# v7-flex2811.net
KiCad netlist of a schematic drawn in EAGLE
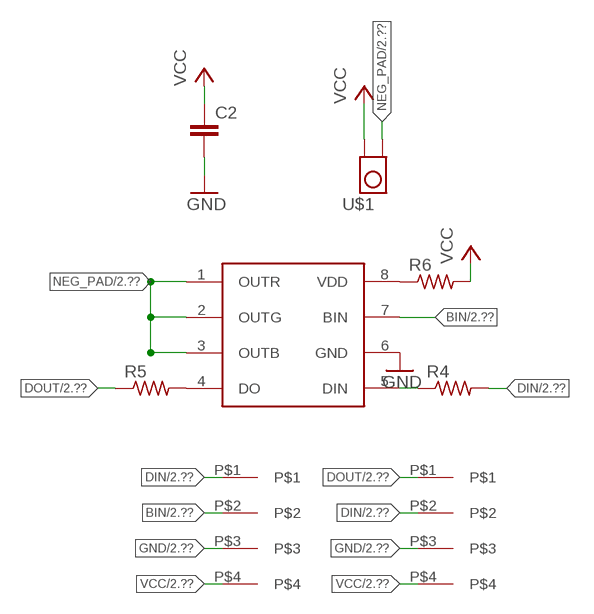
[diagram p0: schematic, sheet 1]
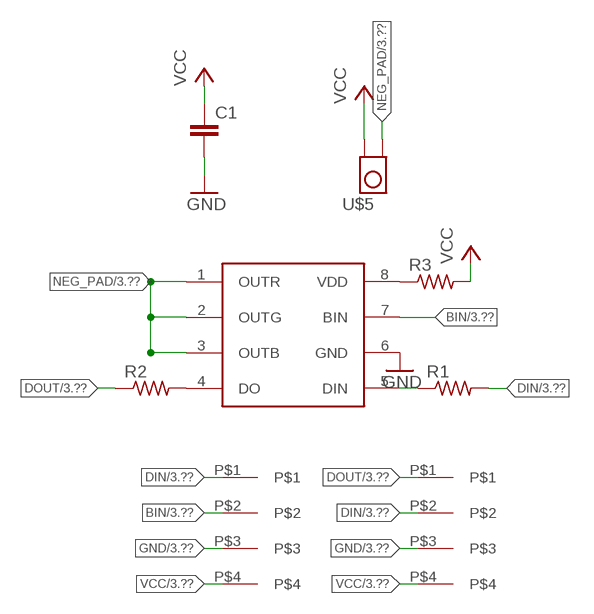
[diagram p1: schematic, sheet 2]
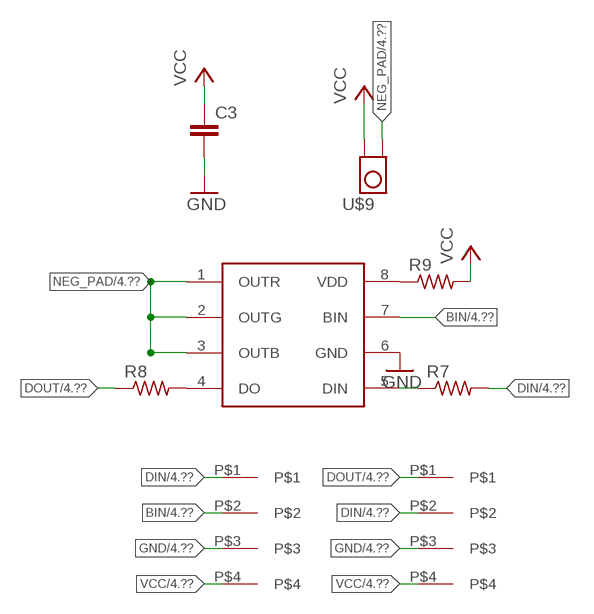
[diagram p2: schematic, sheet 3]
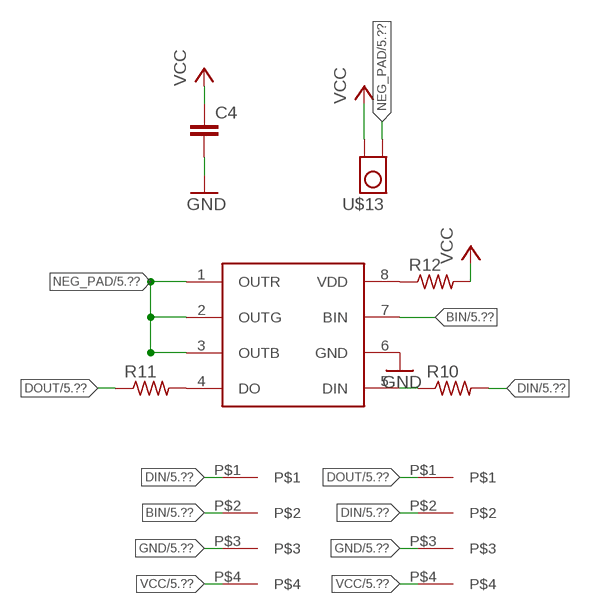
[diagram p3: schematic, sheet 4]
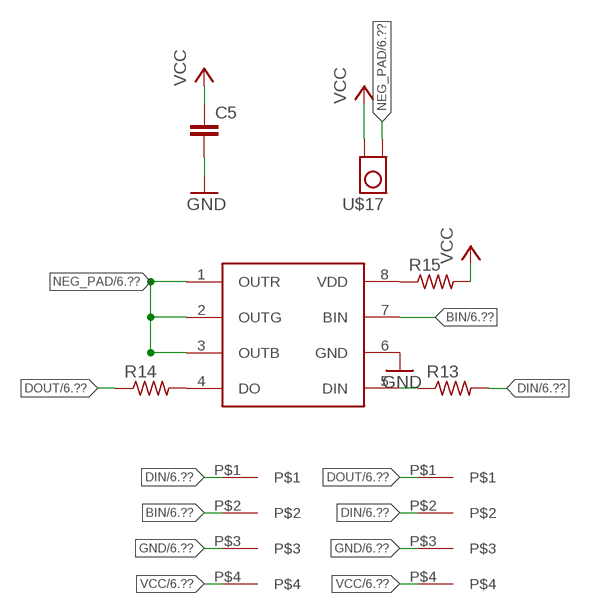
[diagram p4: schematic, sheet 5]
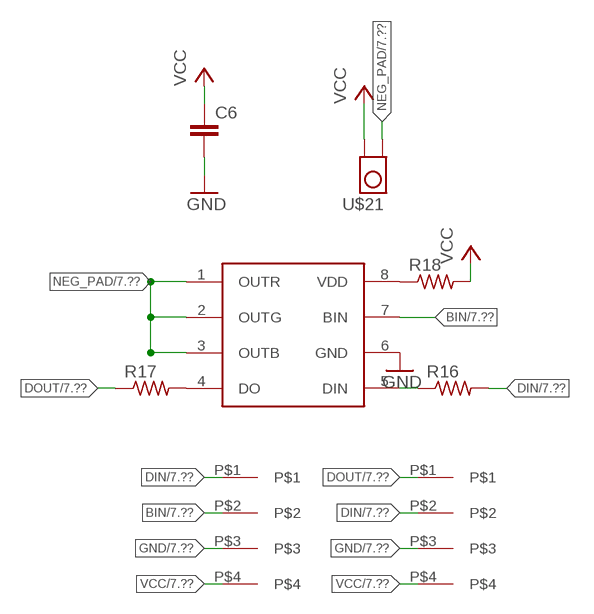
[diagram p5: schematic, sheet 6]
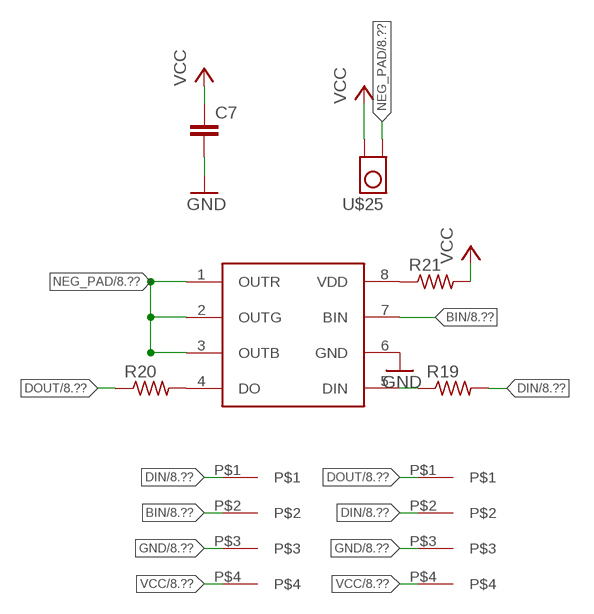
[diagram p6: schematic, sheet 7]
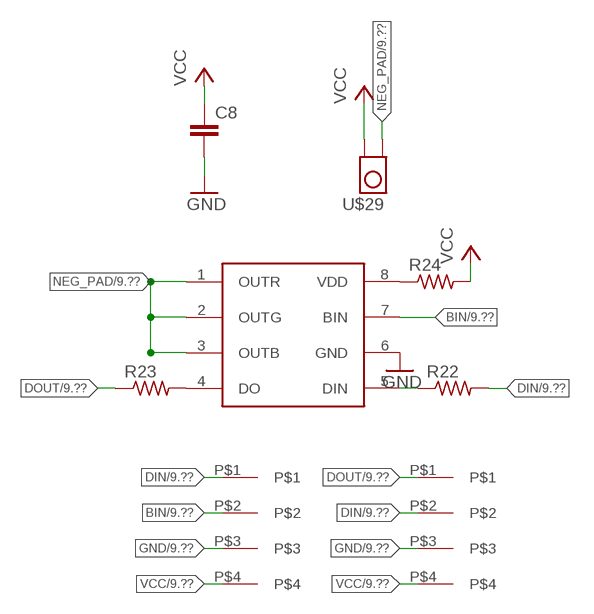
[diagram p7: schematic, sheet 8]
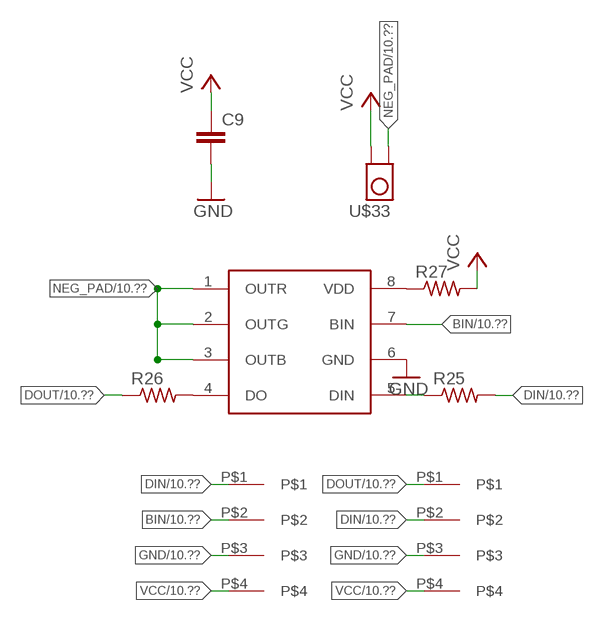
[diagram p8: schematic, sheet 9]
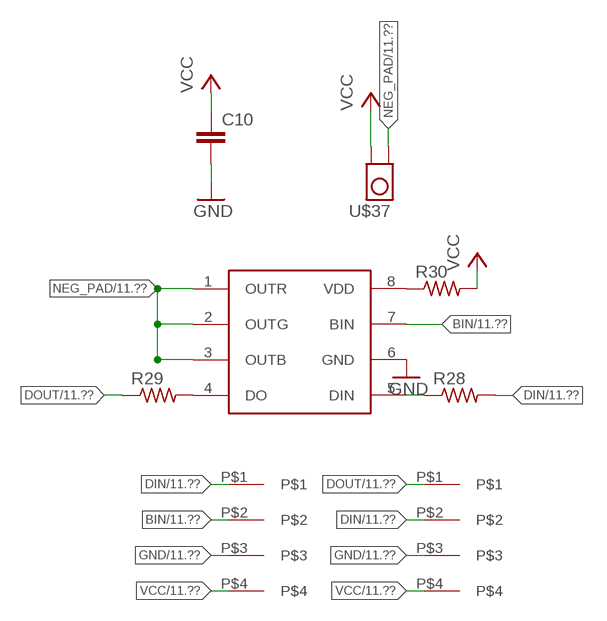
[diagram p9: schematic, sheet 10]
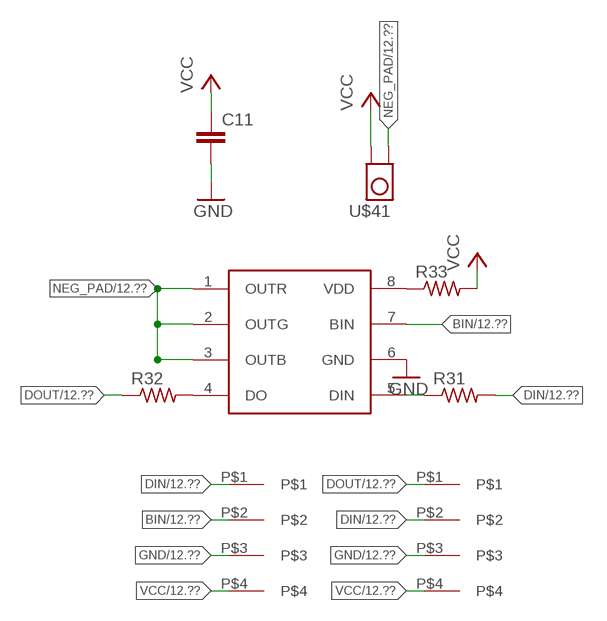
[diagram p10: schematic, sheet 11]
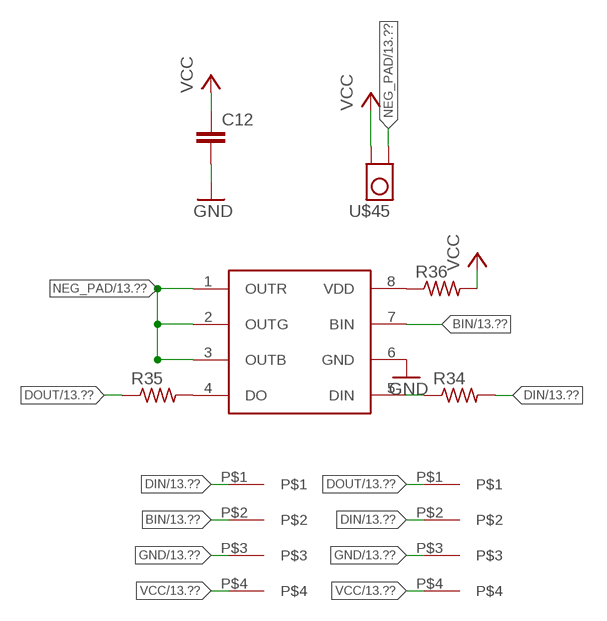
[diagram p11: schematic, sheet 12]
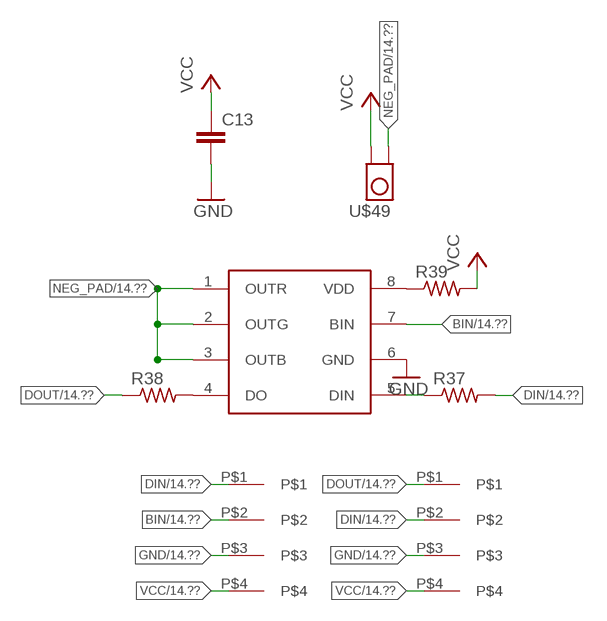
[diagram p12: schematic, sheet 13]
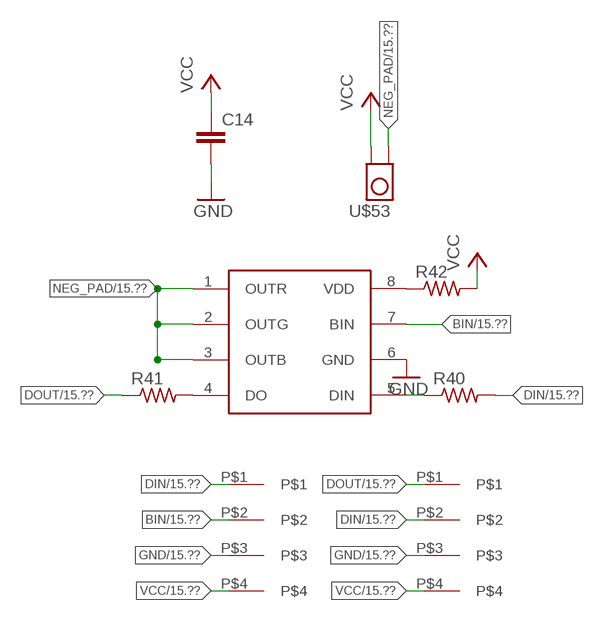
[diagram p13: schematic, sheet 14]
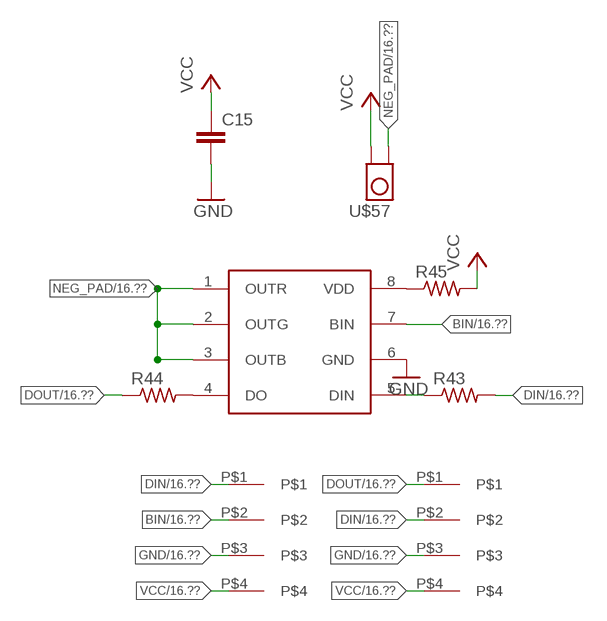
[diagram p14: schematic, sheet 15]
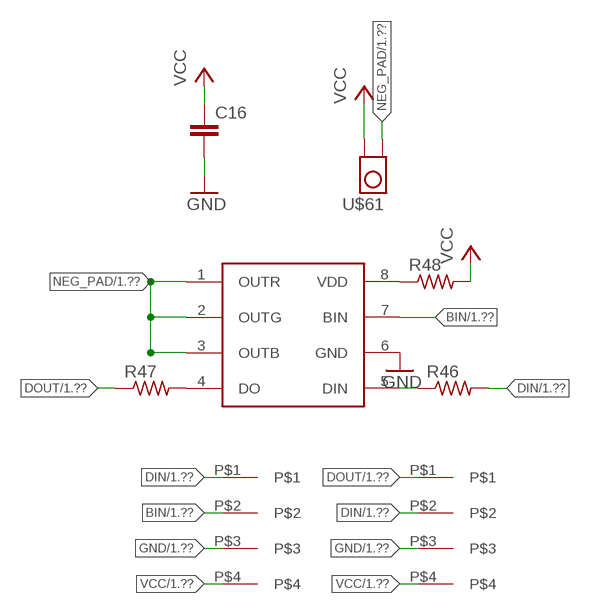
[diagram p15: schematic, sheet 16]

(export (version "E")
  (design (tool "Eeschema 10.0.6"))
  (components
    (comp (ref "C2")
      (value "C-EUC0201")
      (footprint "eagle-import:C0201")
      (libsource (lib "eagle-import") (part "C-EUC0201"))
    )
    (comp (ref "R4")
      (value "R-US_R0201")
      (footprint "eagle-import:R0201")
      (libsource (lib "eagle-import") (part "R-US_R0201"))
    )
    (comp (ref "R5")
      (value "R-US_R0201")
      (footprint "eagle-import:R0201")
      (libsource (lib "eagle-import") (part "R-US_R0201"))
    )
    (comp (ref "R6")
      (value "R-US_R0201")
      (footprint "eagle-import:R0201")
      (libsource (lib "eagle-import") (part "R-US_R0201"))
    )
    (comp (ref "U$1")
      (value "TP_4MM_MED_PAD")
      (footprint "eagle-import:TP_4MM_MED_PAD")
      (libsource (lib "eagle-import") (part "TP_4MM_MED_PAD"))
    )
    (comp (ref "U$2")
      (value "WS2818")
      (footprint "eagle-import:SO08")
      (libsource (lib "eagle-import") (part "WS2818"))
    )
    (comp (ref "U$3")
      (value "4PAD")
      (footprint "eagle-import:4PAD")
      (libsource (lib "eagle-import") (part "4PAD"))
    )
    (comp (ref "U$4")
      (value "4PAD")
      (footprint "eagle-import:4PAD")
      (libsource (lib "eagle-import") (part "4PAD"))
    )
    (comp (ref "C9")
      (value "C-EUC0201")
      (footprint "eagle-import:C0201")
      (libsource (lib "eagle-import") (part "C-EUC0201"))
    )
    (comp (ref "R25")
      (value "R-US_R0201")
      (footprint "eagle-import:R0201")
      (libsource (lib "eagle-import") (part "R-US_R0201"))
    )
    (comp (ref "R26")
      (value "R-US_R0201")
      (footprint "eagle-import:R0201")
      (libsource (lib "eagle-import") (part "R-US_R0201"))
    )
    (comp (ref "R27")
      (value "R-US_R0201")
      (footprint "eagle-import:R0201")
      (libsource (lib "eagle-import") (part "R-US_R0201"))
    )
    (comp (ref "U$33")
      (value "TP_4MM_MED_PAD")
      (footprint "eagle-import:TP_4MM_MED_PAD")
      (libsource (lib "eagle-import") (part "TP_4MM_MED_PAD"))
    )
    (comp (ref "U$34")
      (value "WS2818")
      (footprint "eagle-import:SO08")
      (libsource (lib "eagle-import") (part "WS2818"))
    )
    (comp (ref "U$35")
      (value "4PAD")
      (footprint "eagle-import:4PAD")
      (libsource (lib "eagle-import") (part "4PAD"))
    )
    (comp (ref "U$36")
      (value "4PAD")
      (footprint "eagle-import:4PAD")
      (libsource (lib "eagle-import") (part "4PAD"))
    )
    (comp (ref "C4")
      (value "C-EUC0201")
      (footprint "eagle-import:C0201")
      (libsource (lib "eagle-import") (part "C-EUC0201"))
    )
    (comp (ref "R10")
      (value "R-US_R0201")
      (footprint "eagle-import:R0201")
      (libsource (lib "eagle-import") (part "R-US_R0201"))
    )
    (comp (ref "R11")
      (value "R-US_R0201")
      (footprint "eagle-import:R0201")
      (libsource (lib "eagle-import") (part "R-US_R0201"))
    )
    (comp (ref "R12")
      (value "R-US_R0201")
      (footprint "eagle-import:R0201")
      (libsource (lib "eagle-import") (part "R-US_R0201"))
    )
    (comp (ref "U$13")
      (value "TP_4MM_MED_PAD")
      (footprint "eagle-import:TP_4MM_MED_PAD")
      (libsource (lib "eagle-import") (part "TP_4MM_MED_PAD"))
    )
    (comp (ref "U$14")
      (value "WS2818")
      (footprint "eagle-import:SO08")
      (libsource (lib "eagle-import") (part "WS2818"))
    )
    (comp (ref "U$15")
      (value "4PAD")
      (footprint "eagle-import:4PAD")
      (libsource (lib "eagle-import") (part "4PAD"))
    )
    (comp (ref "U$16")
      (value "4PAD")
      (footprint "eagle-import:4PAD")
      (libsource (lib "eagle-import") (part "4PAD"))
    )
    (comp (ref "C12")
      (value "C-EUC0201")
      (footprint "eagle-import:C0201")
      (libsource (lib "eagle-import") (part "C-EUC0201"))
    )
    (comp (ref "R34")
      (value "R-US_R0201")
      (footprint "eagle-import:R0201")
      (libsource (lib "eagle-import") (part "R-US_R0201"))
    )
    (comp (ref "R35")
      (value "R-US_R0201")
      (footprint "eagle-import:R0201")
      (libsource (lib "eagle-import") (part "R-US_R0201"))
    )
    (comp (ref "R36")
      (value "R-US_R0201")
      (footprint "eagle-import:R0201")
      (libsource (lib "eagle-import") (part "R-US_R0201"))
    )
    (comp (ref "U$45")
      (value "TP_4MM_MED_PAD")
      (footprint "eagle-import:TP_4MM_MED_PAD")
      (libsource (lib "eagle-import") (part "TP_4MM_MED_PAD"))
    )
    (comp (ref "U$46")
      (value "WS2818")
      (footprint "eagle-import:SO08")
      (libsource (lib "eagle-import") (part "WS2818"))
    )
    (comp (ref "U$47")
      (value "4PAD")
      (footprint "eagle-import:4PAD")
      (libsource (lib "eagle-import") (part "4PAD"))
    )
    (comp (ref "U$48")
      (value "4PAD")
      (footprint "eagle-import:4PAD")
      (libsource (lib "eagle-import") (part "4PAD"))
    )
    (comp (ref "C10")
      (value "C-EUC0201")
      (footprint "eagle-import:C0201")
      (libsource (lib "eagle-import") (part "C-EUC0201"))
    )
    (comp (ref "R28")
      (value "R-US_R0201")
      (footprint "eagle-import:R0201")
      (libsource (lib "eagle-import") (part "R-US_R0201"))
    )
    (comp (ref "R29")
      (value "R-US_R0201")
      (footprint "eagle-import:R0201")
      (libsource (lib "eagle-import") (part "R-US_R0201"))
    )
    (comp (ref "R30")
      (value "R-US_R0201")
      (footprint "eagle-import:R0201")
      (libsource (lib "eagle-import") (part "R-US_R0201"))
    )
    (comp (ref "U$37")
      (value "TP_4MM_MED_PAD")
      (footprint "eagle-import:TP_4MM_MED_PAD")
      (libsource (lib "eagle-import") (part "TP_4MM_MED_PAD"))
    )
    (comp (ref "U$38")
      (value "WS2818")
      (footprint "eagle-import:SO08")
      (libsource (lib "eagle-import") (part "WS2818"))
    )
    (comp (ref "U$39")
      (value "4PAD")
      (footprint "eagle-import:4PAD")
      (libsource (lib "eagle-import") (part "4PAD"))
    )
    (comp (ref "U$40")
      (value "4PAD")
      (footprint "eagle-import:4PAD")
      (libsource (lib "eagle-import") (part "4PAD"))
    )
    (comp (ref "C1")
      (value "C-EUC0201")
      (footprint "eagle-import:C0201")
      (libsource (lib "eagle-import") (part "C-EUC0201"))
    )
    (comp (ref "R1")
      (value "R-US_R0201")
      (footprint "eagle-import:R0201")
      (libsource (lib "eagle-import") (part "R-US_R0201"))
    )
    (comp (ref "R2")
      (value "R-US_R0201")
      (footprint "eagle-import:R0201")
      (libsource (lib "eagle-import") (part "R-US_R0201"))
    )
    (comp (ref "R3")
      (value "R-US_R0201")
      (footprint "eagle-import:R0201")
      (libsource (lib "eagle-import") (part "R-US_R0201"))
    )
    (comp (ref "U$5")
      (value "TP_4MM_MED_PAD")
      (footprint "eagle-import:TP_4MM_MED_PAD")
      (libsource (lib "eagle-import") (part "TP_4MM_MED_PAD"))
    )
    (comp (ref "U$6")
      (value "WS2818")
      (footprint "eagle-import:SO08")
      (libsource (lib "eagle-import") (part "WS2818"))
    )
    (comp (ref "U$7")
      (value "4PAD")
      (footprint "eagle-import:4PAD")
      (libsource (lib "eagle-import") (part "4PAD"))
    )
    (comp (ref "U$8")
      (value "4PAD")
      (footprint "eagle-import:4PAD")
      (libsource (lib "eagle-import") (part "4PAD"))
    )
    (comp (ref "C13")
      (value "C-EUC0201")
      (footprint "eagle-import:C0201")
      (libsource (lib "eagle-import") (part "C-EUC0201"))
    )
    (comp (ref "R37")
      (value "R-US_R0201")
      (footprint "eagle-import:R0201")
      (libsource (lib "eagle-import") (part "R-US_R0201"))
    )
    (comp (ref "R38")
      (value "R-US_R0201")
      (footprint "eagle-import:R0201")
      (libsource (lib "eagle-import") (part "R-US_R0201"))
    )
    (comp (ref "R39")
      (value "R-US_R0201")
      (footprint "eagle-import:R0201")
      (libsource (lib "eagle-import") (part "R-US_R0201"))
    )
    (comp (ref "U$49")
      (value "TP_4MM_MED_PAD")
      (footprint "eagle-import:TP_4MM_MED_PAD")
      (libsource (lib "eagle-import") (part "TP_4MM_MED_PAD"))
    )
    (comp (ref "U$50")
      (value "WS2818")
      (footprint "eagle-import:SO08")
      (libsource (lib "eagle-import") (part "WS2818"))
    )
    (comp (ref "U$51")
      (value "4PAD")
      (footprint "eagle-import:4PAD")
      (libsource (lib "eagle-import") (part "4PAD"))
    )
    (comp (ref "U$52")
      (value "4PAD")
      (footprint "eagle-import:4PAD")
      (libsource (lib "eagle-import") (part "4PAD"))
    )
    (comp (ref "C6")
      (value "C-EUC0201")
      (footprint "eagle-import:C0201")
      (libsource (lib "eagle-import") (part "C-EUC0201"))
    )
    (comp (ref "R16")
      (value "R-US_R0201")
      (footprint "eagle-import:R0201")
      (libsource (lib "eagle-import") (part "R-US_R0201"))
    )
    (comp (ref "R17")
      (value "R-US_R0201")
      (footprint "eagle-import:R0201")
      (libsource (lib "eagle-import") (part "R-US_R0201"))
    )
    (comp (ref "R18")
      (value "R-US_R0201")
      (footprint "eagle-import:R0201")
      (libsource (lib "eagle-import") (part "R-US_R0201"))
    )
    (comp (ref "U$21")
      (value "TP_4MM_MED_PAD")
      (footprint "eagle-import:TP_4MM_MED_PAD")
      (libsource (lib "eagle-import") (part "TP_4MM_MED_PAD"))
    )
    (comp (ref "U$22")
      (value "WS2818")
      (footprint "eagle-import:SO08")
      (libsource (lib "eagle-import") (part "WS2818"))
    )
    (comp (ref "U$23")
      (value "4PAD")
      (footprint "eagle-import:4PAD")
      (libsource (lib "eagle-import") (part "4PAD"))
    )
    (comp (ref "U$24")
      (value "4PAD")
      (footprint "eagle-import:4PAD")
      (libsource (lib "eagle-import") (part "4PAD"))
    )
    (comp (ref "C5")
      (value "C-EUC0201")
      (footprint "eagle-import:C0201")
      (libsource (lib "eagle-import") (part "C-EUC0201"))
    )
    (comp (ref "R13")
      (value "R-US_R0201")
      (footprint "eagle-import:R0201")
      (libsource (lib "eagle-import") (part "R-US_R0201"))
    )
    (comp (ref "R14")
      (value "R-US_R0201")
      (footprint "eagle-import:R0201")
      (libsource (lib "eagle-import") (part "R-US_R0201"))
    )
    (comp (ref "R15")
      (value "R-US_R0201")
      (footprint "eagle-import:R0201")
      (libsource (lib "eagle-import") (part "R-US_R0201"))
    )
    (comp (ref "U$17")
      (value "TP_4MM_MED_PAD")
      (footprint "eagle-import:TP_4MM_MED_PAD")
      (libsource (lib "eagle-import") (part "TP_4MM_MED_PAD"))
    )
    (comp (ref "U$18")
      (value "WS2818")
      (footprint "eagle-import:SO08")
      (libsource (lib "eagle-import") (part "WS2818"))
    )
    (comp (ref "U$19")
      (value "4PAD")
      (footprint "eagle-import:4PAD")
      (libsource (lib "eagle-import") (part "4PAD"))
    )
    (comp (ref "U$20")
      (value "4PAD")
      (footprint "eagle-import:4PAD")
      (libsource (lib "eagle-import") (part "4PAD"))
    )
    (comp (ref "C14")
      (value "C-EUC0201")
      (footprint "eagle-import:C0201")
      (libsource (lib "eagle-import") (part "C-EUC0201"))
    )
    (comp (ref "R40")
      (value "R-US_R0201")
      (footprint "eagle-import:R0201")
      (libsource (lib "eagle-import") (part "R-US_R0201"))
    )
    (comp (ref "R41")
      (value "R-US_R0201")
      (footprint "eagle-import:R0201")
      (libsource (lib "eagle-import") (part "R-US_R0201"))
    )
    (comp (ref "R42")
      (value "R-US_R0201")
      (footprint "eagle-import:R0201")
      (libsource (lib "eagle-import") (part "R-US_R0201"))
    )
    (comp (ref "U$53")
      (value "TP_4MM_MED_PAD")
      (footprint "eagle-import:TP_4MM_MED_PAD")
      (libsource (lib "eagle-import") (part "TP_4MM_MED_PAD"))
    )
    (comp (ref "U$54")
      (value "WS2818")
      (footprint "eagle-import:SO08")
      (libsource (lib "eagle-import") (part "WS2818"))
    )
    (comp (ref "U$55")
      (value "4PAD")
      (footprint "eagle-import:4PAD")
      (libsource (lib "eagle-import") (part "4PAD"))
    )
    (comp (ref "U$56")
      (value "4PAD")
      (footprint "eagle-import:4PAD")
      (libsource (lib "eagle-import") (part "4PAD"))
    )
    (comp (ref "C11")
      (value "C-EUC0201")
      (footprint "eagle-import:C0201")
      (libsource (lib "eagle-import") (part "C-EUC0201"))
    )
    (comp (ref "R31")
      (value "R-US_R0201")
      (footprint "eagle-import:R0201")
      (libsource (lib "eagle-import") (part "R-US_R0201"))
    )
    (comp (ref "R32")
      (value "R-US_R0201")
      (footprint "eagle-import:R0201")
      (libsource (lib "eagle-import") (part "R-US_R0201"))
    )
    (comp (ref "R33")
      (value "R-US_R0201")
      (footprint "eagle-import:R0201")
      (libsource (lib "eagle-import") (part "R-US_R0201"))
    )
    (comp (ref "U$41")
      (value "TP_4MM_MED_PAD")
      (footprint "eagle-import:TP_4MM_MED_PAD")
      (libsource (lib "eagle-import") (part "TP_4MM_MED_PAD"))
    )
    (comp (ref "U$42")
      (value "WS2818")
      (footprint "eagle-import:SO08")
      (libsource (lib "eagle-import") (part "WS2818"))
    )
    (comp (ref "U$43")
      (value "4PAD")
      (footprint "eagle-import:4PAD")
      (libsource (lib "eagle-import") (part "4PAD"))
    )
    (comp (ref "U$44")
      (value "4PAD")
      (footprint "eagle-import:4PAD")
      (libsource (lib "eagle-import") (part "4PAD"))
    )
    (comp (ref "C16")
      (value "C-EUC0201")
      (footprint "eagle-import:C0201")
      (libsource (lib "eagle-import") (part "C-EUC0201"))
    )
    (comp (ref "R46")
      (value "R-US_R0201")
      (footprint "eagle-import:R0201")
      (libsource (lib "eagle-import") (part "R-US_R0201"))
    )
    (comp (ref "R47")
      (value "R-US_R0201")
      (footprint "eagle-import:R0201")
      (libsource (lib "eagle-import") (part "R-US_R0201"))
    )
    (comp (ref "R48")
      (value "R-US_R0201")
      (footprint "eagle-import:R0201")
      (libsource (lib "eagle-import") (part "R-US_R0201"))
    )
    (comp (ref "U$61")
      (value "TP_4MM_MED_PAD")
      (footprint "eagle-import:TP_4MM_MED_PAD")
      (libsource (lib "eagle-import") (part "TP_4MM_MED_PAD"))
    )
    (comp (ref "U$62")
      (value "WS2818")
      (footprint "eagle-import:SO08")
      (libsource (lib "eagle-import") (part "WS2818"))
    )
    (comp (ref "U$63")
      (value "4PAD")
      (footprint "eagle-import:4PAD")
      (libsource (lib "eagle-import") (part "4PAD"))
    )
    (comp (ref "U$64")
      (value "4PAD")
      (footprint "eagle-import:4PAD")
      (libsource (lib "eagle-import") (part "4PAD"))
    )
    (comp (ref "C3")
      (value "C-EUC0201")
      (footprint "eagle-import:C0201")
      (libsource (lib "eagle-import") (part "C-EUC0201"))
    )
    (comp (ref "R7")
      (value "R-US_R0201")
      (footprint "eagle-import:R0201")
      (libsource (lib "eagle-import") (part "R-US_R0201"))
    )
    (comp (ref "R8")
      (value "R-US_R0201")
      (footprint "eagle-import:R0201")
      (libsource (lib "eagle-import") (part "R-US_R0201"))
    )
    (comp (ref "R9")
      (value "R-US_R0201")
      (footprint "eagle-import:R0201")
      (libsource (lib "eagle-import") (part "R-US_R0201"))
    )
    (comp (ref "U$9")
      (value "TP_4MM_MED_PAD")
      (footprint "eagle-import:TP_4MM_MED_PAD")
      (libsource (lib "eagle-import") (part "TP_4MM_MED_PAD"))
    )
    (comp (ref "U$10")
      (value "WS2818")
      (footprint "eagle-import:SO08")
      (libsource (lib "eagle-import") (part "WS2818"))
    )
    (comp (ref "U$11")
      (value "4PAD")
      (footprint "eagle-import:4PAD")
      (libsource (lib "eagle-import") (part "4PAD"))
    )
    (comp (ref "U$12")
      (value "4PAD")
      (footprint "eagle-import:4PAD")
      (libsource (lib "eagle-import") (part "4PAD"))
    )
    (comp (ref "C8")
      (value "C-EUC0201")
      (footprint "eagle-import:C0201")
      (libsource (lib "eagle-import") (part "C-EUC0201"))
    )
    (comp (ref "R22")
      (value "R-US_R0201")
      (footprint "eagle-import:R0201")
      (libsource (lib "eagle-import") (part "R-US_R0201"))
    )
    (comp (ref "R23")
      (value "R-US_R0201")
      (footprint "eagle-import:R0201")
      (libsource (lib "eagle-import") (part "R-US_R0201"))
    )
    (comp (ref "R24")
      (value "R-US_R0201")
      (footprint "eagle-import:R0201")
      (libsource (lib "eagle-import") (part "R-US_R0201"))
    )
    (comp (ref "U$29")
      (value "TP_4MM_MED_PAD")
      (footprint "eagle-import:TP_4MM_MED_PAD")
      (libsource (lib "eagle-import") (part "TP_4MM_MED_PAD"))
    )
    (comp (ref "U$30")
      (value "WS2818")
      (footprint "eagle-import:SO08")
      (libsource (lib "eagle-import") (part "WS2818"))
    )
    (comp (ref "U$31")
      (value "4PAD")
      (footprint "eagle-import:4PAD")
      (libsource (lib "eagle-import") (part "4PAD"))
    )
    (comp (ref "U$32")
      (value "4PAD")
      (footprint "eagle-import:4PAD")
      (libsource (lib "eagle-import") (part "4PAD"))
    )
    (comp (ref "C7")
      (value "C-EUC0201")
      (footprint "eagle-import:C0201")
      (libsource (lib "eagle-import") (part "C-EUC0201"))
    )
    (comp (ref "R19")
      (value "R-US_R0201")
      (footprint "eagle-import:R0201")
      (libsource (lib "eagle-import") (part "R-US_R0201"))
    )
    (comp (ref "R20")
      (value "R-US_R0201")
      (footprint "eagle-import:R0201")
      (libsource (lib "eagle-import") (part "R-US_R0201"))
    )
    (comp (ref "R21")
      (value "R-US_R0201")
      (footprint "eagle-import:R0201")
      (libsource (lib "eagle-import") (part "R-US_R0201"))
    )
    (comp (ref "U$25")
      (value "TP_4MM_MED_PAD")
      (footprint "eagle-import:TP_4MM_MED_PAD")
      (libsource (lib "eagle-import") (part "TP_4MM_MED_PAD"))
    )
    (comp (ref "U$26")
      (value "WS2818")
      (footprint "eagle-import:SO08")
      (libsource (lib "eagle-import") (part "WS2818"))
    )
    (comp (ref "U$27")
      (value "4PAD")
      (footprint "eagle-import:4PAD")
      (libsource (lib "eagle-import") (part "4PAD"))
    )
    (comp (ref "U$28")
      (value "4PAD")
      (footprint "eagle-import:4PAD")
      (libsource (lib "eagle-import") (part "4PAD"))
    )
    (comp (ref "C15")
      (value "C-EUC0201")
      (footprint "eagle-import:C0201")
      (libsource (lib "eagle-import") (part "C-EUC0201"))
    )
    (comp (ref "R43")
      (value "R-US_R0201")
      (footprint "eagle-import:R0201")
      (libsource (lib "eagle-import") (part "R-US_R0201"))
    )
    (comp (ref "R44")
      (value "R-US_R0201")
      (footprint "eagle-import:R0201")
      (libsource (lib "eagle-import") (part "R-US_R0201"))
    )
    (comp (ref "R45")
      (value "R-US_R0201")
      (footprint "eagle-import:R0201")
      (libsource (lib "eagle-import") (part "R-US_R0201"))
    )
    (comp (ref "U$57")
      (value "TP_4MM_MED_PAD")
      (footprint "eagle-import:TP_4MM_MED_PAD")
      (libsource (lib "eagle-import") (part "TP_4MM_MED_PAD"))
    )
    (comp (ref "U$58")
      (value "WS2818")
      (footprint "eagle-import:SO08")
      (libsource (lib "eagle-import") (part "WS2818"))
    )
    (comp (ref "U$59")
      (value "4PAD")
      (footprint "eagle-import:4PAD")
      (libsource (lib "eagle-import") (part "4PAD"))
    )
    (comp (ref "U$60")
      (value "4PAD")
      (footprint "eagle-import:4PAD")
      (libsource (lib "eagle-import") (part "4PAD"))
    )
  )
  (nets
    (net (code "1") (name "BIN") (class "Default")
      (node (ref "U$10") (pin "7") (pinfunction "BIN_7") (pintype "bidirectional"))
      (node (ref "U$11") (pin "P$2") (pinfunction "P$2_P$2") (pintype "bidirectional"))
      (node (ref "U$14") (pin "7") (pinfunction "BIN_7") (pintype "bidirectional"))
      (node (ref "U$15") (pin "P$2") (pinfunction "P$2_P$2") (pintype "bidirectional"))
      (node (ref "U$18") (pin "7") (pinfunction "BIN_7") (pintype "bidirectional"))
      (node (ref "U$19") (pin "P$2") (pinfunction "P$2_P$2") (pintype "bidirectional"))
      (node (ref "U$2") (pin "7") (pinfunction "BIN_7") (pintype "bidirectional"))
      (node (ref "U$22") (pin "7") (pinfunction "BIN_7") (pintype "bidirectional"))
      (node (ref "U$23") (pin "P$2") (pinfunction "P$2_P$2") (pintype "bidirectional"))
      (node (ref "U$26") (pin "7") (pinfunction "BIN_7") (pintype "bidirectional"))
      (node (ref "U$27") (pin "P$2") (pinfunction "P$2_P$2") (pintype "bidirectional"))
      (node (ref "U$3") (pin "P$2") (pinfunction "P$2_P$2") (pintype "bidirectional"))
      (node (ref "U$30") (pin "7") (pinfunction "BIN_7") (pintype "bidirectional"))
      (node (ref "U$31") (pin "P$2") (pinfunction "P$2_P$2") (pintype "bidirectional"))
      (node (ref "U$34") (pin "7") (pinfunction "BIN_7") (pintype "bidirectional"))
      (node (ref "U$35") (pin "P$2") (pinfunction "P$2_P$2") (pintype "bidirectional"))
      (node (ref "U$38") (pin "7") (pinfunction "BIN_7") (pintype "bidirectional"))
      (node (ref "U$39") (pin "P$2") (pinfunction "P$2_P$2") (pintype "bidirectional"))
      (node (ref "U$42") (pin "7") (pinfunction "BIN_7") (pintype "bidirectional"))
      (node (ref "U$43") (pin "P$2") (pinfunction "P$2_P$2") (pintype "bidirectional"))
      (node (ref "U$46") (pin "7") (pinfunction "BIN_7") (pintype "bidirectional"))
      (node (ref "U$47") (pin "P$2") (pinfunction "P$2_P$2") (pintype "bidirectional"))
      (node (ref "U$50") (pin "7") (pinfunction "BIN_7") (pintype "bidirectional"))
      (node (ref "U$51") (pin "P$2") (pinfunction "P$2_P$2") (pintype "bidirectional"))
      (node (ref "U$54") (pin "7") (pinfunction "BIN_7") (pintype "bidirectional"))
      (node (ref "U$55") (pin "P$2") (pinfunction "P$2_P$2") (pintype "bidirectional"))
      (node (ref "U$58") (pin "7") (pinfunction "BIN_7") (pintype "bidirectional"))
      (node (ref "U$59") (pin "P$2") (pinfunction "P$2_P$2") (pintype "bidirectional"))
      (node (ref "U$6") (pin "7") (pinfunction "BIN_7") (pintype "bidirectional"))
      (node (ref "U$62") (pin "7") (pinfunction "BIN_7") (pintype "bidirectional"))
      (node (ref "U$63") (pin "P$2") (pinfunction "P$2_P$2") (pintype "bidirectional"))
      (node (ref "U$7") (pin "P$2") (pinfunction "P$2_P$2") (pintype "bidirectional"))
    )
    (net (code "2") (name "DIN") (class "Default")
      (node (ref "R1") (pin "2") (pinfunction "2_2") (pintype "passive"))
      (node (ref "R10") (pin "2") (pinfunction "2_2") (pintype "passive"))
      (node (ref "R13") (pin "2") (pinfunction "2_2") (pintype "passive"))
      (node (ref "R16") (pin "2") (pinfunction "2_2") (pintype "passive"))
      (node (ref "R19") (pin "2") (pinfunction "2_2") (pintype "passive"))
      (node (ref "R22") (pin "2") (pinfunction "2_2") (pintype "passive"))
      (node (ref "R25") (pin "2") (pinfunction "2_2") (pintype "passive"))
      (node (ref "R28") (pin "2") (pinfunction "2_2") (pintype "passive"))
      (node (ref "R31") (pin "2") (pinfunction "2_2") (pintype "passive"))
      (node (ref "R34") (pin "2") (pinfunction "2_2") (pintype "passive"))
      (node (ref "R37") (pin "2") (pinfunction "2_2") (pintype "passive"))
      (node (ref "R4") (pin "2") (pinfunction "2_2") (pintype "passive"))
      (node (ref "R40") (pin "2") (pinfunction "2_2") (pintype "passive"))
      (node (ref "R43") (pin "2") (pinfunction "2_2") (pintype "passive"))
      (node (ref "R46") (pin "2") (pinfunction "2_2") (pintype "passive"))
      (node (ref "R7") (pin "2") (pinfunction "2_2") (pintype "passive"))
      (node (ref "U$11") (pin "P$1") (pinfunction "P$1_P$1") (pintype "bidirectional"))
      (node (ref "U$12") (pin "P$2") (pinfunction "P$2_P$2") (pintype "bidirectional"))
      (node (ref "U$15") (pin "P$1") (pinfunction "P$1_P$1") (pintype "bidirectional"))
      (node (ref "U$16") (pin "P$2") (pinfunction "P$2_P$2") (pintype "bidirectional"))
      (node (ref "U$19") (pin "P$1") (pinfunction "P$1_P$1") (pintype "bidirectional"))
      (node (ref "U$20") (pin "P$2") (pinfunction "P$2_P$2") (pintype "bidirectional"))
      (node (ref "U$23") (pin "P$1") (pinfunction "P$1_P$1") (pintype "bidirectional"))
      (node (ref "U$24") (pin "P$2") (pinfunction "P$2_P$2") (pintype "bidirectional"))
      (node (ref "U$27") (pin "P$1") (pinfunction "P$1_P$1") (pintype "bidirectional"))
      (node (ref "U$28") (pin "P$2") (pinfunction "P$2_P$2") (pintype "bidirectional"))
      (node (ref "U$3") (pin "P$1") (pinfunction "P$1_P$1") (pintype "bidirectional"))
      (node (ref "U$31") (pin "P$1") (pinfunction "P$1_P$1") (pintype "bidirectional"))
      (node (ref "U$32") (pin "P$2") (pinfunction "P$2_P$2") (pintype "bidirectional"))
      (node (ref "U$35") (pin "P$1") (pinfunction "P$1_P$1") (pintype "bidirectional"))
      (node (ref "U$36") (pin "P$2") (pinfunction "P$2_P$2") (pintype "bidirectional"))
      (node (ref "U$39") (pin "P$1") (pinfunction "P$1_P$1") (pintype "bidirectional"))
      (node (ref "U$4") (pin "P$2") (pinfunction "P$2_P$2") (pintype "bidirectional"))
      (node (ref "U$40") (pin "P$2") (pinfunction "P$2_P$2") (pintype "bidirectional"))
      (node (ref "U$43") (pin "P$1") (pinfunction "P$1_P$1") (pintype "bidirectional"))
      (node (ref "U$44") (pin "P$2") (pinfunction "P$2_P$2") (pintype "bidirectional"))
      (node (ref "U$47") (pin "P$1") (pinfunction "P$1_P$1") (pintype "bidirectional"))
      (node (ref "U$48") (pin "P$2") (pinfunction "P$2_P$2") (pintype "bidirectional"))
      (node (ref "U$51") (pin "P$1") (pinfunction "P$1_P$1") (pintype "bidirectional"))
      (node (ref "U$52") (pin "P$2") (pinfunction "P$2_P$2") (pintype "bidirectional"))
      (node (ref "U$55") (pin "P$1") (pinfunction "P$1_P$1") (pintype "bidirectional"))
      (node (ref "U$56") (pin "P$2") (pinfunction "P$2_P$2") (pintype "bidirectional"))
      (node (ref "U$59") (pin "P$1") (pinfunction "P$1_P$1") (pintype "bidirectional"))
      (node (ref "U$60") (pin "P$2") (pinfunction "P$2_P$2") (pintype "bidirectional"))
      (node (ref "U$63") (pin "P$1") (pinfunction "P$1_P$1") (pintype "bidirectional"))
      (node (ref "U$64") (pin "P$2") (pinfunction "P$2_P$2") (pintype "bidirectional"))
      (node (ref "U$7") (pin "P$1") (pinfunction "P$1_P$1") (pintype "bidirectional"))
      (node (ref "U$8") (pin "P$2") (pinfunction "P$2_P$2") (pintype "bidirectional"))
    )
    (net (code "3") (name "DOUT") (class "Default")
      (node (ref "R11") (pin "1") (pinfunction "1_1") (pintype "passive"))
      (node (ref "R14") (pin "1") (pinfunction "1_1") (pintype "passive"))
      (node (ref "R17") (pin "1") (pinfunction "1_1") (pintype "passive"))
      (node (ref "R2") (pin "1") (pinfunction "1_1") (pintype "passive"))
      (node (ref "R20") (pin "1") (pinfunction "1_1") (pintype "passive"))
      (node (ref "R23") (pin "1") (pinfunction "1_1") (pintype "passive"))
      (node (ref "R26") (pin "1") (pinfunction "1_1") (pintype "passive"))
      (node (ref "R29") (pin "1") (pinfunction "1_1") (pintype "passive"))
      (node (ref "R32") (pin "1") (pinfunction "1_1") (pintype "passive"))
      (node (ref "R35") (pin "1") (pinfunction "1_1") (pintype "passive"))
      (node (ref "R38") (pin "1") (pinfunction "1_1") (pintype "passive"))
      (node (ref "R41") (pin "1") (pinfunction "1_1") (pintype "passive"))
      (node (ref "R44") (pin "1") (pinfunction "1_1") (pintype "passive"))
      (node (ref "R47") (pin "1") (pinfunction "1_1") (pintype "passive"))
      (node (ref "R5") (pin "1") (pinfunction "1_1") (pintype "passive"))
      (node (ref "R8") (pin "1") (pinfunction "1_1") (pintype "passive"))
      (node (ref "U$12") (pin "P$1") (pinfunction "P$1_P$1") (pintype "bidirectional"))
      (node (ref "U$16") (pin "P$1") (pinfunction "P$1_P$1") (pintype "bidirectional"))
      (node (ref "U$20") (pin "P$1") (pinfunction "P$1_P$1") (pintype "bidirectional"))
      (node (ref "U$24") (pin "P$1") (pinfunction "P$1_P$1") (pintype "bidirectional"))
      (node (ref "U$28") (pin "P$1") (pinfunction "P$1_P$1") (pintype "bidirectional"))
      (node (ref "U$32") (pin "P$1") (pinfunction "P$1_P$1") (pintype "bidirectional"))
      (node (ref "U$36") (pin "P$1") (pinfunction "P$1_P$1") (pintype "bidirectional"))
      (node (ref "U$4") (pin "P$1") (pinfunction "P$1_P$1") (pintype "bidirectional"))
      (node (ref "U$40") (pin "P$1") (pinfunction "P$1_P$1") (pintype "bidirectional"))
      (node (ref "U$44") (pin "P$1") (pinfunction "P$1_P$1") (pintype "bidirectional"))
      (node (ref "U$48") (pin "P$1") (pinfunction "P$1_P$1") (pintype "bidirectional"))
      (node (ref "U$52") (pin "P$1") (pinfunction "P$1_P$1") (pintype "bidirectional"))
      (node (ref "U$56") (pin "P$1") (pinfunction "P$1_P$1") (pintype "bidirectional"))
      (node (ref "U$60") (pin "P$1") (pinfunction "P$1_P$1") (pintype "bidirectional"))
      (node (ref "U$64") (pin "P$1") (pinfunction "P$1_P$1") (pintype "bidirectional"))
      (node (ref "U$8") (pin "P$1") (pinfunction "P$1_P$1") (pintype "bidirectional"))
    )
    (net (code "4") (name "GND") (class "Default")
      (node (ref "C1") (pin "2") (pinfunction "2_2") (pintype "passive"))
      (node (ref "C10") (pin "2") (pinfunction "2_2") (pintype "passive"))
      (node (ref "C11") (pin "2") (pinfunction "2_2") (pintype "passive"))
      (node (ref "C12") (pin "2") (pinfunction "2_2") (pintype "passive"))
      (node (ref "C13") (pin "2") (pinfunction "2_2") (pintype "passive"))
      (node (ref "C14") (pin "2") (pinfunction "2_2") (pintype "passive"))
      (node (ref "C15") (pin "2") (pinfunction "2_2") (pintype "passive"))
      (node (ref "C16") (pin "2") (pinfunction "2_2") (pintype "passive"))
      (node (ref "C2") (pin "2") (pinfunction "2_2") (pintype "passive"))
      (node (ref "C3") (pin "2") (pinfunction "2_2") (pintype "passive"))
      (node (ref "C4") (pin "2") (pinfunction "2_2") (pintype "passive"))
      (node (ref "C5") (pin "2") (pinfunction "2_2") (pintype "passive"))
      (node (ref "C6") (pin "2") (pinfunction "2_2") (pintype "passive"))
      (node (ref "C7") (pin "2") (pinfunction "2_2") (pintype "passive"))
      (node (ref "C8") (pin "2") (pinfunction "2_2") (pintype "passive"))
      (node (ref "C9") (pin "2") (pinfunction "2_2") (pintype "passive"))
      (node (ref "U$10") (pin "6") (pinfunction "GND_6") (pintype "bidirectional"))
      (node (ref "U$11") (pin "P$3") (pinfunction "P$3_P$3") (pintype "bidirectional"))
      (node (ref "U$12") (pin "P$3") (pinfunction "P$3_P$3") (pintype "bidirectional"))
      (node (ref "U$14") (pin "6") (pinfunction "GND_6") (pintype "bidirectional"))
      (node (ref "U$15") (pin "P$3") (pinfunction "P$3_P$3") (pintype "bidirectional"))
      (node (ref "U$16") (pin "P$3") (pinfunction "P$3_P$3") (pintype "bidirectional"))
      (node (ref "U$18") (pin "6") (pinfunction "GND_6") (pintype "bidirectional"))
      (node (ref "U$19") (pin "P$3") (pinfunction "P$3_P$3") (pintype "bidirectional"))
      (node (ref "U$2") (pin "6") (pinfunction "GND_6") (pintype "bidirectional"))
      (node (ref "U$20") (pin "P$3") (pinfunction "P$3_P$3") (pintype "bidirectional"))
      (node (ref "U$22") (pin "6") (pinfunction "GND_6") (pintype "bidirectional"))
      (node (ref "U$23") (pin "P$3") (pinfunction "P$3_P$3") (pintype "bidirectional"))
      (node (ref "U$24") (pin "P$3") (pinfunction "P$3_P$3") (pintype "bidirectional"))
      (node (ref "U$26") (pin "6") (pinfunction "GND_6") (pintype "bidirectional"))
      (node (ref "U$27") (pin "P$3") (pinfunction "P$3_P$3") (pintype "bidirectional"))
      (node (ref "U$28") (pin "P$3") (pinfunction "P$3_P$3") (pintype "bidirectional"))
      (node (ref "U$3") (pin "P$3") (pinfunction "P$3_P$3") (pintype "bidirectional"))
      (node (ref "U$30") (pin "6") (pinfunction "GND_6") (pintype "bidirectional"))
      (node (ref "U$31") (pin "P$3") (pinfunction "P$3_P$3") (pintype "bidirectional"))
      (node (ref "U$32") (pin "P$3") (pinfunction "P$3_P$3") (pintype "bidirectional"))
      (node (ref "U$34") (pin "6") (pinfunction "GND_6") (pintype "bidirectional"))
      (node (ref "U$35") (pin "P$3") (pinfunction "P$3_P$3") (pintype "bidirectional"))
      (node (ref "U$36") (pin "P$3") (pinfunction "P$3_P$3") (pintype "bidirectional"))
      (node (ref "U$38") (pin "6") (pinfunction "GND_6") (pintype "bidirectional"))
      (node (ref "U$39") (pin "P$3") (pinfunction "P$3_P$3") (pintype "bidirectional"))
      (node (ref "U$4") (pin "P$3") (pinfunction "P$3_P$3") (pintype "bidirectional"))
      (node (ref "U$40") (pin "P$3") (pinfunction "P$3_P$3") (pintype "bidirectional"))
      (node (ref "U$42") (pin "6") (pinfunction "GND_6") (pintype "bidirectional"))
      (node (ref "U$43") (pin "P$3") (pinfunction "P$3_P$3") (pintype "bidirectional"))
      (node (ref "U$44") (pin "P$3") (pinfunction "P$3_P$3") (pintype "bidirectional"))
      (node (ref "U$46") (pin "6") (pinfunction "GND_6") (pintype "bidirectional"))
      (node (ref "U$47") (pin "P$3") (pinfunction "P$3_P$3") (pintype "bidirectional"))
      (node (ref "U$48") (pin "P$3") (pinfunction "P$3_P$3") (pintype "bidirectional"))
      (node (ref "U$50") (pin "6") (pinfunction "GND_6") (pintype "bidirectional"))
      (node (ref "U$51") (pin "P$3") (pinfunction "P$3_P$3") (pintype "bidirectional"))
      (node (ref "U$52") (pin "P$3") (pinfunction "P$3_P$3") (pintype "bidirectional"))
      (node (ref "U$54") (pin "6") (pinfunction "GND_6") (pintype "bidirectional"))
      (node (ref "U$55") (pin "P$3") (pinfunction "P$3_P$3") (pintype "bidirectional"))
      (node (ref "U$56") (pin "P$3") (pinfunction "P$3_P$3") (pintype "bidirectional"))
      (node (ref "U$58") (pin "6") (pinfunction "GND_6") (pintype "bidirectional"))
      (node (ref "U$59") (pin "P$3") (pinfunction "P$3_P$3") (pintype "bidirectional"))
      (node (ref "U$6") (pin "6") (pinfunction "GND_6") (pintype "bidirectional"))
      (node (ref "U$60") (pin "P$3") (pinfunction "P$3_P$3") (pintype "bidirectional"))
      (node (ref "U$62") (pin "6") (pinfunction "GND_6") (pintype "bidirectional"))
      (node (ref "U$63") (pin "P$3") (pinfunction "P$3_P$3") (pintype "bidirectional"))
      (node (ref "U$64") (pin "P$3") (pinfunction "P$3_P$3") (pintype "bidirectional"))
      (node (ref "U$7") (pin "P$3") (pinfunction "P$3_P$3") (pintype "bidirectional"))
      (node (ref "U$8") (pin "P$3") (pinfunction "P$3_P$3") (pintype "bidirectional"))
    )
    (net (code "5") (name "NEG_PAD") (class "Default")
      (node (ref "U$1") (pin "P$1") (pinfunction "0_P$1") (pintype "bidirectional"))
      (node (ref "U$10") (pin "1") (pinfunction "OUTR_1") (pintype "bidirectional"))
      (node (ref "U$10") (pin "2") (pinfunction "OUTG_2") (pintype "bidirectional"))
      (node (ref "U$10") (pin "3") (pinfunction "OUTB_3") (pintype "bidirectional"))
      (node (ref "U$13") (pin "P$1") (pinfunction "0_P$1") (pintype "bidirectional"))
      (node (ref "U$14") (pin "1") (pinfunction "OUTR_1") (pintype "bidirectional"))
      (node (ref "U$14") (pin "2") (pinfunction "OUTG_2") (pintype "bidirectional"))
      (node (ref "U$14") (pin "3") (pinfunction "OUTB_3") (pintype "bidirectional"))
      (node (ref "U$17") (pin "P$1") (pinfunction "0_P$1") (pintype "bidirectional"))
      (node (ref "U$18") (pin "1") (pinfunction "OUTR_1") (pintype "bidirectional"))
      (node (ref "U$18") (pin "2") (pinfunction "OUTG_2") (pintype "bidirectional"))
      (node (ref "U$18") (pin "3") (pinfunction "OUTB_3") (pintype "bidirectional"))
      (node (ref "U$2") (pin "1") (pinfunction "OUTR_1") (pintype "bidirectional"))
      (node (ref "U$2") (pin "2") (pinfunction "OUTG_2") (pintype "bidirectional"))
      (node (ref "U$2") (pin "3") (pinfunction "OUTB_3") (pintype "bidirectional"))
      (node (ref "U$21") (pin "P$1") (pinfunction "0_P$1") (pintype "bidirectional"))
      (node (ref "U$22") (pin "1") (pinfunction "OUTR_1") (pintype "bidirectional"))
      (node (ref "U$22") (pin "2") (pinfunction "OUTG_2") (pintype "bidirectional"))
      (node (ref "U$22") (pin "3") (pinfunction "OUTB_3") (pintype "bidirectional"))
      (node (ref "U$25") (pin "P$1") (pinfunction "0_P$1") (pintype "bidirectional"))
      (node (ref "U$26") (pin "1") (pinfunction "OUTR_1") (pintype "bidirectional"))
      (node (ref "U$26") (pin "2") (pinfunction "OUTG_2") (pintype "bidirectional"))
      (node (ref "U$26") (pin "3") (pinfunction "OUTB_3") (pintype "bidirectional"))
      (node (ref "U$29") (pin "P$1") (pinfunction "0_P$1") (pintype "bidirectional"))
      (node (ref "U$30") (pin "1") (pinfunction "OUTR_1") (pintype "bidirectional"))
      (node (ref "U$30") (pin "2") (pinfunction "OUTG_2") (pintype "bidirectional"))
      (node (ref "U$30") (pin "3") (pinfunction "OUTB_3") (pintype "bidirectional"))
      (node (ref "U$33") (pin "P$1") (pinfunction "0_P$1") (pintype "bidirectional"))
      (node (ref "U$34") (pin "1") (pinfunction "OUTR_1") (pintype "bidirectional"))
      (node (ref "U$34") (pin "2") (pinfunction "OUTG_2") (pintype "bidirectional"))
      (node (ref "U$34") (pin "3") (pinfunction "OUTB_3") (pintype "bidirectional"))
      (node (ref "U$37") (pin "P$1") (pinfunction "0_P$1") (pintype "bidirectional"))
      (node (ref "U$38") (pin "1") (pinfunction "OUTR_1") (pintype "bidirectional"))
      (node (ref "U$38") (pin "2") (pinfunction "OUTG_2") (pintype "bidirectional"))
      (node (ref "U$38") (pin "3") (pinfunction "OUTB_3") (pintype "bidirectional"))
      (node (ref "U$41") (pin "P$1") (pinfunction "0_P$1") (pintype "bidirectional"))
      (node (ref "U$42") (pin "1") (pinfunction "OUTR_1") (pintype "bidirectional"))
      (node (ref "U$42") (pin "2") (pinfunction "OUTG_2") (pintype "bidirectional"))
      (node (ref "U$42") (pin "3") (pinfunction "OUTB_3") (pintype "bidirectional"))
      (node (ref "U$45") (pin "P$1") (pinfunction "0_P$1") (pintype "bidirectional"))
      (node (ref "U$46") (pin "1") (pinfunction "OUTR_1") (pintype "bidirectional"))
      (node (ref "U$46") (pin "2") (pinfunction "OUTG_2") (pintype "bidirectional"))
      (node (ref "U$46") (pin "3") (pinfunction "OUTB_3") (pintype "bidirectional"))
      (node (ref "U$49") (pin "P$1") (pinfunction "0_P$1") (pintype "bidirectional"))
      (node (ref "U$5") (pin "P$1") (pinfunction "0_P$1") (pintype "bidirectional"))
      (node (ref "U$50") (pin "1") (pinfunction "OUTR_1") (pintype "bidirectional"))
      (node (ref "U$50") (pin "2") (pinfunction "OUTG_2") (pintype "bidirectional"))
      (node (ref "U$50") (pin "3") (pinfunction "OUTB_3") (pintype "bidirectional"))
      (node (ref "U$53") (pin "P$1") (pinfunction "0_P$1") (pintype "bidirectional"))
      (node (ref "U$54") (pin "1") (pinfunction "OUTR_1") (pintype "bidirectional"))
      (node (ref "U$54") (pin "2") (pinfunction "OUTG_2") (pintype "bidirectional"))
      (node (ref "U$54") (pin "3") (pinfunction "OUTB_3") (pintype "bidirectional"))
      (node (ref "U$57") (pin "P$1") (pinfunction "0_P$1") (pintype "bidirectional"))
      (node (ref "U$58") (pin "1") (pinfunction "OUTR_1") (pintype "bidirectional"))
      (node (ref "U$58") (pin "2") (pinfunction "OUTG_2") (pintype "bidirectional"))
      (node (ref "U$58") (pin "3") (pinfunction "OUTB_3") (pintype "bidirectional"))
      (node (ref "U$6") (pin "1") (pinfunction "OUTR_1") (pintype "bidirectional"))
      (node (ref "U$6") (pin "2") (pinfunction "OUTG_2") (pintype "bidirectional"))
      (node (ref "U$6") (pin "3") (pinfunction "OUTB_3") (pintype "bidirectional"))
      (node (ref "U$61") (pin "P$1") (pinfunction "0_P$1") (pintype "bidirectional"))
      (node (ref "U$62") (pin "1") (pinfunction "OUTR_1") (pintype "bidirectional"))
      (node (ref "U$62") (pin "2") (pinfunction "OUTG_2") (pintype "bidirectional"))
      (node (ref "U$62") (pin "3") (pinfunction "OUTB_3") (pintype "bidirectional"))
      (node (ref "U$9") (pin "P$1") (pinfunction "0_P$1") (pintype "bidirectional"))
    )
    (net (code "6") (name "Net-(U$2-DIN)") (class "Default")
      (node (ref "R4") (pin "1") (pinfunction "1_1") (pintype "passive"))
      (node (ref "U$2") (pin "5") (pinfunction "DIN_5") (pintype "bidirectional"))
    )
    (net (code "7") (name "Net-(U$2-DO)") (class "Default")
      (node (ref "R5") (pin "2") (pinfunction "2_2") (pintype "passive"))
      (node (ref "U$2") (pin "4") (pinfunction "DO_4") (pintype "bidirectional"))
    )
    (net (code "8") (name "Net-(U$2-VDD)") (class "Default")
      (node (ref "R6") (pin "1") (pinfunction "1_1") (pintype "passive"))
      (node (ref "U$2") (pin "8") (pinfunction "VDD_8") (pintype "bidirectional"))
    )
    (net (code "9") (name "Net-(U$6-DIN)") (class "Default")
      (node (ref "R1") (pin "1") (pinfunction "1_1") (pintype "passive"))
      (node (ref "U$6") (pin "5") (pinfunction "DIN_5") (pintype "bidirectional"))
    )
    (net (code "10") (name "Net-(U$6-DO)") (class "Default")
      (node (ref "R2") (pin "2") (pinfunction "2_2") (pintype "passive"))
      (node (ref "U$6") (pin "4") (pinfunction "DO_4") (pintype "bidirectional"))
    )
    (net (code "11") (name "Net-(U$6-VDD)") (class "Default")
      (node (ref "R3") (pin "1") (pinfunction "1_1") (pintype "passive"))
      (node (ref "U$6") (pin "8") (pinfunction "VDD_8") (pintype "bidirectional"))
    )
    (net (code "12") (name "Net-(U$10-DIN)") (class "Default")
      (node (ref "R7") (pin "1") (pinfunction "1_1") (pintype "passive"))
      (node (ref "U$10") (pin "5") (pinfunction "DIN_5") (pintype "bidirectional"))
    )
    (net (code "13") (name "Net-(U$10-DO)") (class "Default")
      (node (ref "R8") (pin "2") (pinfunction "2_2") (pintype "passive"))
      (node (ref "U$10") (pin "4") (pinfunction "DO_4") (pintype "bidirectional"))
    )
    (net (code "14") (name "Net-(U$10-VDD)") (class "Default")
      (node (ref "R9") (pin "1") (pinfunction "1_1") (pintype "passive"))
      (node (ref "U$10") (pin "8") (pinfunction "VDD_8") (pintype "bidirectional"))
    )
    (net (code "15") (name "Net-(U$14-DIN)") (class "Default")
      (node (ref "R10") (pin "1") (pinfunction "1_1") (pintype "passive"))
      (node (ref "U$14") (pin "5") (pinfunction "DIN_5") (pintype "bidirectional"))
    )
    (net (code "16") (name "Net-(U$14-DO)") (class "Default")
      (node (ref "R11") (pin "2") (pinfunction "2_2") (pintype "passive"))
      (node (ref "U$14") (pin "4") (pinfunction "DO_4") (pintype "bidirectional"))
    )
    (net (code "17") (name "Net-(U$14-VDD)") (class "Default")
      (node (ref "R12") (pin "1") (pinfunction "1_1") (pintype "passive"))
      (node (ref "U$14") (pin "8") (pinfunction "VDD_8") (pintype "bidirectional"))
    )
    (net (code "18") (name "Net-(U$18-DIN)") (class "Default")
      (node (ref "R13") (pin "1") (pinfunction "1_1") (pintype "passive"))
      (node (ref "U$18") (pin "5") (pinfunction "DIN_5") (pintype "bidirectional"))
    )
    (net (code "19") (name "Net-(U$18-DO)") (class "Default")
      (node (ref "R14") (pin "2") (pinfunction "2_2") (pintype "passive"))
      (node (ref "U$18") (pin "4") (pinfunction "DO_4") (pintype "bidirectional"))
    )
    (net (code "20") (name "Net-(U$18-VDD)") (class "Default")
      (node (ref "R15") (pin "1") (pinfunction "1_1") (pintype "passive"))
      (node (ref "U$18") (pin "8") (pinfunction "VDD_8") (pintype "bidirectional"))
    )
    (net (code "21") (name "Net-(U$22-DIN)") (class "Default")
      (node (ref "R16") (pin "1") (pinfunction "1_1") (pintype "passive"))
      (node (ref "U$22") (pin "5") (pinfunction "DIN_5") (pintype "bidirectional"))
    )
    (net (code "22") (name "Net-(U$22-DO)") (class "Default")
      (node (ref "R17") (pin "2") (pinfunction "2_2") (pintype "passive"))
      (node (ref "U$22") (pin "4") (pinfunction "DO_4") (pintype "bidirectional"))
    )
    (net (code "23") (name "Net-(U$22-VDD)") (class "Default")
      (node (ref "R18") (pin "1") (pinfunction "1_1") (pintype "passive"))
      (node (ref "U$22") (pin "8") (pinfunction "VDD_8") (pintype "bidirectional"))
    )
    (net (code "24") (name "Net-(U$26-DIN)") (class "Default")
      (node (ref "R19") (pin "1") (pinfunction "1_1") (pintype "passive"))
      (node (ref "U$26") (pin "5") (pinfunction "DIN_5") (pintype "bidirectional"))
    )
    (net (code "25") (name "Net-(U$26-DO)") (class "Default")
      (node (ref "R20") (pin "2") (pinfunction "2_2") (pintype "passive"))
      (node (ref "U$26") (pin "4") (pinfunction "DO_4") (pintype "bidirectional"))
    )
    (net (code "26") (name "Net-(U$26-VDD)") (class "Default")
      (node (ref "R21") (pin "1") (pinfunction "1_1") (pintype "passive"))
      (node (ref "U$26") (pin "8") (pinfunction "VDD_8") (pintype "bidirectional"))
    )
    (net (code "27") (name "Net-(U$30-DIN)") (class "Default")
      (node (ref "R22") (pin "1") (pinfunction "1_1") (pintype "passive"))
      (node (ref "U$30") (pin "5") (pinfunction "DIN_5") (pintype "bidirectional"))
    )
    (net (code "28") (name "Net-(U$30-DO)") (class "Default")
      (node (ref "R23") (pin "2") (pinfunction "2_2") (pintype "passive"))
      (node (ref "U$30") (pin "4") (pinfunction "DO_4") (pintype "bidirectional"))
    )
    (net (code "29") (name "Net-(U$30-VDD)") (class "Default")
      (node (ref "R24") (pin "1") (pinfunction "1_1") (pintype "passive"))
      (node (ref "U$30") (pin "8") (pinfunction "VDD_8") (pintype "bidirectional"))
    )
    (net (code "30") (name "Net-(U$34-DIN)") (class "Default")
      (node (ref "R25") (pin "1") (pinfunction "1_1") (pintype "passive"))
      (node (ref "U$34") (pin "5") (pinfunction "DIN_5") (pintype "bidirectional"))
    )
    (net (code "31") (name "Net-(U$34-DO)") (class "Default")
      (node (ref "R26") (pin "2") (pinfunction "2_2") (pintype "passive"))
      (node (ref "U$34") (pin "4") (pinfunction "DO_4") (pintype "bidirectional"))
    )
    (net (code "32") (name "Net-(U$34-VDD)") (class "Default")
      (node (ref "R27") (pin "1") (pinfunction "1_1") (pintype "passive"))
      (node (ref "U$34") (pin "8") (pinfunction "VDD_8") (pintype "bidirectional"))
    )
    (net (code "33") (name "Net-(U$38-DIN)") (class "Default")
      (node (ref "R28") (pin "1") (pinfunction "1_1") (pintype "passive"))
      (node (ref "U$38") (pin "5") (pinfunction "DIN_5") (pintype "bidirectional"))
    )
    (net (code "34") (name "Net-(U$38-DO)") (class "Default")
      (node (ref "R29") (pin "2") (pinfunction "2_2") (pintype "passive"))
      (node (ref "U$38") (pin "4") (pinfunction "DO_4") (pintype "bidirectional"))
    )
    (net (code "35") (name "Net-(U$38-VDD)") (class "Default")
      (node (ref "R30") (pin "1") (pinfunction "1_1") (pintype "passive"))
      (node (ref "U$38") (pin "8") (pinfunction "VDD_8") (pintype "bidirectional"))
    )
    (net (code "36") (name "Net-(U$42-DIN)") (class "Default")
      (node (ref "R31") (pin "1") (pinfunction "1_1") (pintype "passive"))
      (node (ref "U$42") (pin "5") (pinfunction "DIN_5") (pintype "bidirectional"))
    )
    (net (code "37") (name "Net-(U$42-DO)") (class "Default")
      (node (ref "R32") (pin "2") (pinfunction "2_2") (pintype "passive"))
      (node (ref "U$42") (pin "4") (pinfunction "DO_4") (pintype "bidirectional"))
    )
    (net (code "38") (name "Net-(U$42-VDD)") (class "Default")
      (node (ref "R33") (pin "1") (pinfunction "1_1") (pintype "passive"))
      (node (ref "U$42") (pin "8") (pinfunction "VDD_8") (pintype "bidirectional"))
    )
    (net (code "39") (name "Net-(U$46-DIN)") (class "Default")
      (node (ref "R34") (pin "1") (pinfunction "1_1") (pintype "passive"))
      (node (ref "U$46") (pin "5") (pinfunction "DIN_5") (pintype "bidirectional"))
    )
    (net (code "40") (name "Net-(U$46-DO)") (class "Default")
      (node (ref "R35") (pin "2") (pinfunction "2_2") (pintype "passive"))
      (node (ref "U$46") (pin "4") (pinfunction "DO_4") (pintype "bidirectional"))
    )
    (net (code "41") (name "Net-(U$46-VDD)") (class "Default")
      (node (ref "R36") (pin "1") (pinfunction "1_1") (pintype "passive"))
      (node (ref "U$46") (pin "8") (pinfunction "VDD_8") (pintype "bidirectional"))
    )
    (net (code "42") (name "Net-(U$50-DIN)") (class "Default")
      (node (ref "R37") (pin "1") (pinfunction "1_1") (pintype "passive"))
      (node (ref "U$50") (pin "5") (pinfunction "DIN_5") (pintype "bidirectional"))
    )
    (net (code "43") (name "Net-(U$50-DO)") (class "Default")
      (node (ref "R38") (pin "2") (pinfunction "2_2") (pintype "passive"))
      (node (ref "U$50") (pin "4") (pinfunction "DO_4") (pintype "bidirectional"))
    )
    (net (code "44") (name "Net-(U$50-VDD)") (class "Default")
      (node (ref "R39") (pin "1") (pinfunction "1_1") (pintype "passive"))
      (node (ref "U$50") (pin "8") (pinfunction "VDD_8") (pintype "bidirectional"))
    )
    (net (code "45") (name "Net-(U$54-DIN)") (class "Default")
      (node (ref "R40") (pin "1") (pinfunction "1_1") (pintype "passive"))
      (node (ref "U$54") (pin "5") (pinfunction "DIN_5") (pintype "bidirectional"))
    )
    (net (code "46") (name "Net-(U$54-DO)") (class "Default")
      (node (ref "R41") (pin "2") (pinfunction "2_2") (pintype "passive"))
      (node (ref "U$54") (pin "4") (pinfunction "DO_4") (pintype "bidirectional"))
    )
    (net (code "47") (name "Net-(U$54-VDD)") (class "Default")
      (node (ref "R42") (pin "1") (pinfunction "1_1") (pintype "passive"))
      (node (ref "U$54") (pin "8") (pinfunction "VDD_8") (pintype "bidirectional"))
    )
    (net (code "48") (name "Net-(U$58-DIN)") (class "Default")
      (node (ref "R43") (pin "1") (pinfunction "1_1") (pintype "passive"))
      (node (ref "U$58") (pin "5") (pinfunction "DIN_5") (pintype "bidirectional"))
    )
    (net (code "49") (name "Net-(U$58-DO)") (class "Default")
      (node (ref "R44") (pin "2") (pinfunction "2_2") (pintype "passive"))
      (node (ref "U$58") (pin "4") (pinfunction "DO_4") (pintype "bidirectional"))
    )
    (net (code "50") (name "Net-(U$58-VDD)") (class "Default")
      (node (ref "R45") (pin "1") (pinfunction "1_1") (pintype "passive"))
      (node (ref "U$58") (pin "8") (pinfunction "VDD_8") (pintype "bidirectional"))
    )
    (net (code "51") (name "Net-(U$62-DIN)") (class "Default")
      (node (ref "R46") (pin "1") (pinfunction "1_1") (pintype "passive"))
      (node (ref "U$62") (pin "5") (pinfunction "DIN_5") (pintype "bidirectional"))
    )
    (net (code "52") (name "Net-(U$62-DO)") (class "Default")
      (node (ref "R47") (pin "2") (pinfunction "2_2") (pintype "passive"))
      (node (ref "U$62") (pin "4") (pinfunction "DO_4") (pintype "bidirectional"))
    )
    (net (code "53") (name "Net-(U$62-VDD)") (class "Default")
      (node (ref "R48") (pin "1") (pinfunction "1_1") (pintype "passive"))
      (node (ref "U$62") (pin "8") (pinfunction "VDD_8") (pintype "bidirectional"))
    )
    (net (code "54") (name "VCC") (class "Default")
      (node (ref "C1") (pin "1") (pinfunction "1_1") (pintype "passive"))
      (node (ref "C10") (pin "1") (pinfunction "1_1") (pintype "passive"))
      (node (ref "C11") (pin "1") (pinfunction "1_1") (pintype "passive"))
      (node (ref "C12") (pin "1") (pinfunction "1_1") (pintype "passive"))
      (node (ref "C13") (pin "1") (pinfunction "1_1") (pintype "passive"))
      (node (ref "C14") (pin "1") (pinfunction "1_1") (pintype "passive"))
      (node (ref "C15") (pin "1") (pinfunction "1_1") (pintype "passive"))
      (node (ref "C16") (pin "1") (pinfunction "1_1") (pintype "passive"))
      (node (ref "C2") (pin "1") (pinfunction "1_1") (pintype "passive"))
      (node (ref "C3") (pin "1") (pinfunction "1_1") (pintype "passive"))
      (node (ref "C4") (pin "1") (pinfunction "1_1") (pintype "passive"))
      (node (ref "C5") (pin "1") (pinfunction "1_1") (pintype "passive"))
      (node (ref "C6") (pin "1") (pinfunction "1_1") (pintype "passive"))
      (node (ref "C7") (pin "1") (pinfunction "1_1") (pintype "passive"))
      (node (ref "C8") (pin "1") (pinfunction "1_1") (pintype "passive"))
      (node (ref "C9") (pin "1") (pinfunction "1_1") (pintype "passive"))
      (node (ref "R12") (pin "2") (pinfunction "2_2") (pintype "passive"))
      (node (ref "R15") (pin "2") (pinfunction "2_2") (pintype "passive"))
      (node (ref "R18") (pin "2") (pinfunction "2_2") (pintype "passive"))
      (node (ref "R21") (pin "2") (pinfunction "2_2") (pintype "passive"))
      (node (ref "R24") (pin "2") (pinfunction "2_2") (pintype "passive"))
      (node (ref "R27") (pin "2") (pinfunction "2_2") (pintype "passive"))
      (node (ref "R3") (pin "2") (pinfunction "2_2") (pintype "passive"))
      (node (ref "R30") (pin "2") (pinfunction "2_2") (pintype "passive"))
      (node (ref "R33") (pin "2") (pinfunction "2_2") (pintype "passive"))
      (node (ref "R36") (pin "2") (pinfunction "2_2") (pintype "passive"))
      (node (ref "R39") (pin "2") (pinfunction "2_2") (pintype "passive"))
      (node (ref "R42") (pin "2") (pinfunction "2_2") (pintype "passive"))
      (node (ref "R45") (pin "2") (pinfunction "2_2") (pintype "passive"))
      (node (ref "R48") (pin "2") (pinfunction "2_2") (pintype "passive"))
      (node (ref "R6") (pin "2") (pinfunction "2_2") (pintype "passive"))
      (node (ref "R9") (pin "2") (pinfunction "2_2") (pintype "passive"))
      (node (ref "U$1") (pin "P$2") (pinfunction "1_P$2") (pintype "bidirectional"))
      (node (ref "U$11") (pin "P$4") (pinfunction "P$4_P$4") (pintype "bidirectional"))
      (node (ref "U$12") (pin "P$4") (pinfunction "P$4_P$4") (pintype "bidirectional"))
      (node (ref "U$13") (pin "P$2") (pinfunction "1_P$2") (pintype "bidirectional"))
      (node (ref "U$15") (pin "P$4") (pinfunction "P$4_P$4") (pintype "bidirectional"))
      (node (ref "U$16") (pin "P$4") (pinfunction "P$4_P$4") (pintype "bidirectional"))
      (node (ref "U$17") (pin "P$2") (pinfunction "1_P$2") (pintype "bidirectional"))
      (node (ref "U$19") (pin "P$4") (pinfunction "P$4_P$4") (pintype "bidirectional"))
      (node (ref "U$20") (pin "P$4") (pinfunction "P$4_P$4") (pintype "bidirectional"))
      (node (ref "U$21") (pin "P$2") (pinfunction "1_P$2") (pintype "bidirectional"))
      (node (ref "U$23") (pin "P$4") (pinfunction "P$4_P$4") (pintype "bidirectional"))
      (node (ref "U$24") (pin "P$4") (pinfunction "P$4_P$4") (pintype "bidirectional"))
      (node (ref "U$25") (pin "P$2") (pinfunction "1_P$2") (pintype "bidirectional"))
      (node (ref "U$27") (pin "P$4") (pinfunction "P$4_P$4") (pintype "bidirectional"))
      (node (ref "U$28") (pin "P$4") (pinfunction "P$4_P$4") (pintype "bidirectional"))
      (node (ref "U$29") (pin "P$2") (pinfunction "1_P$2") (pintype "bidirectional"))
      (node (ref "U$3") (pin "P$4") (pinfunction "P$4_P$4") (pintype "bidirectional"))
      (node (ref "U$31") (pin "P$4") (pinfunction "P$4_P$4") (pintype "bidirectional"))
      (node (ref "U$32") (pin "P$4") (pinfunction "P$4_P$4") (pintype "bidirectional"))
      (node (ref "U$33") (pin "P$2") (pinfunction "1_P$2") (pintype "bidirectional"))
      (node (ref "U$35") (pin "P$4") (pinfunction "P$4_P$4") (pintype "bidirectional"))
      (node (ref "U$36") (pin "P$4") (pinfunction "P$4_P$4") (pintype "bidirectional"))
      (node (ref "U$37") (pin "P$2") (pinfunction "1_P$2") (pintype "bidirectional"))
      (node (ref "U$39") (pin "P$4") (pinfunction "P$4_P$4") (pintype "bidirectional"))
      (node (ref "U$4") (pin "P$4") (pinfunction "P$4_P$4") (pintype "bidirectional"))
      (node (ref "U$40") (pin "P$4") (pinfunction "P$4_P$4") (pintype "bidirectional"))
      (node (ref "U$41") (pin "P$2") (pinfunction "1_P$2") (pintype "bidirectional"))
      (node (ref "U$43") (pin "P$4") (pinfunction "P$4_P$4") (pintype "bidirectional"))
      (node (ref "U$44") (pin "P$4") (pinfunction "P$4_P$4") (pintype "bidirectional"))
      (node (ref "U$45") (pin "P$2") (pinfunction "1_P$2") (pintype "bidirectional"))
      (node (ref "U$47") (pin "P$4") (pinfunction "P$4_P$4") (pintype "bidirectional"))
      (node (ref "U$48") (pin "P$4") (pinfunction "P$4_P$4") (pintype "bidirectional"))
      (node (ref "U$49") (pin "P$2") (pinfunction "1_P$2") (pintype "bidirectional"))
      (node (ref "U$5") (pin "P$2") (pinfunction "1_P$2") (pintype "bidirectional"))
      (node (ref "U$51") (pin "P$4") (pinfunction "P$4_P$4") (pintype "bidirectional"))
      (node (ref "U$52") (pin "P$4") (pinfunction "P$4_P$4") (pintype "bidirectional"))
      (node (ref "U$53") (pin "P$2") (pinfunction "1_P$2") (pintype "bidirectional"))
      (node (ref "U$55") (pin "P$4") (pinfunction "P$4_P$4") (pintype "bidirectional"))
      (node (ref "U$56") (pin "P$4") (pinfunction "P$4_P$4") (pintype "bidirectional"))
      (node (ref "U$57") (pin "P$2") (pinfunction "1_P$2") (pintype "bidirectional"))
      (node (ref "U$59") (pin "P$4") (pinfunction "P$4_P$4") (pintype "bidirectional"))
      (node (ref "U$60") (pin "P$4") (pinfunction "P$4_P$4") (pintype "bidirectional"))
      (node (ref "U$61") (pin "P$2") (pinfunction "1_P$2") (pintype "bidirectional"))
      (node (ref "U$63") (pin "P$4") (pinfunction "P$4_P$4") (pintype "bidirectional"))
      (node (ref "U$64") (pin "P$4") (pinfunction "P$4_P$4") (pintype "bidirectional"))
      (node (ref "U$7") (pin "P$4") (pinfunction "P$4_P$4") (pintype "bidirectional"))
      (node (ref "U$8") (pin "P$4") (pinfunction "P$4_P$4") (pintype "bidirectional"))
      (node (ref "U$9") (pin "P$2") (pinfunction "1_P$2") (pintype "bidirectional"))
    )
  )
)
